# dust_sensor.net
KiCad netlist of a schematic drawn in EAGLE
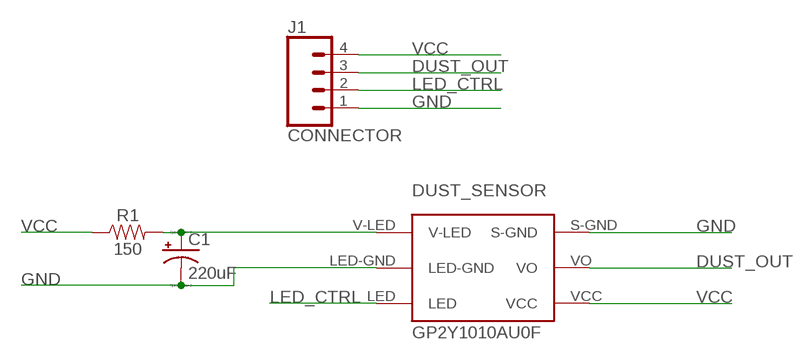
[diagram p0: schematic, sheet 1]

(export (version "E")
  (design (tool "Eeschema 10.0.6"))
  (components
    (comp (ref "C1")
      (value "220uF")
      (footprint "eagle-import:E2,5-6")
      (libsource (lib "eagle-import") (part "CPOL-USE2.5-6"))
    )
    (comp (ref "DUST_SENSOR")
      (value "GP2Y1010AU0F")
      (footprint "eagle-import:GP2Y1010AU0F")
      (libsource (lib "eagle-import") (part "GP2Y1010AU0F"))
    )
    (comp (ref "J1")
      (value "CONNECTOR")
      (footprint "eagle-import:MOLEX-1X4")
      (libsource (lib "eagle-import") (part "CONN_04POLAR"))
    )
    (comp (ref "R1")
      (value "150")
      (footprint "eagle-import:AXIAL-0.3")
      (libsource (lib "eagle-import") (part "100OHM-HORIZ-1/4W-1%"))
    )
  )
  (nets
    (net (code "1") (name "/DUST_OUT") (class "Default")
      (node (ref "DUST_SENSOR") (pin "VO") (pinfunction "VO_VO") (pintype "output"))
      (node (ref "J1") (pin "3") (pinfunction "3_3") (pintype "passive"))
    )
    (net (code "2") (name "/GND") (class "Default")
      (node (ref "C1") (pin "-") (pinfunction "-_-") (pintype "passive"))
      (node (ref "DUST_SENSOR") (pin "LED-GND") (pinfunction "LED-GND_LED-GND") (pintype "power_in"))
      (node (ref "DUST_SENSOR") (pin "S-GND") (pinfunction "S-GND_S-GND") (pintype "power_in"))
      (node (ref "J1") (pin "1") (pinfunction "1_1") (pintype "passive"))
    )
    (net (code "3") (name "/LED_CTRL") (class "Default")
      (node (ref "DUST_SENSOR") (pin "LED") (pinfunction "LED_LED") (pintype "input"))
      (node (ref "J1") (pin "2") (pinfunction "2_2") (pintype "passive"))
    )
    (net (code "4") (name "/VCC") (class "Default")
      (node (ref "DUST_SENSOR") (pin "VCC") (pinfunction "VCC_VCC") (pintype "power_in"))
      (node (ref "J1") (pin "4") (pinfunction "4_4") (pintype "passive"))
      (node (ref "R1") (pin "P$1") (pinfunction "1_P$1") (pintype "passive"))
    )
    (net (code "5") (name "Net-(R1-2)") (class "Default")
      (node (ref "C1") (pin "+") (pinfunction "+_+") (pintype "passive"))
      (node (ref "DUST_SENSOR") (pin "V-LED") (pinfunction "V-LED_V-LED") (pintype "power_in"))
      (node (ref "R1") (pin "P$2") (pinfunction "2_P$2") (pintype "passive"))
    )
  )
)
